# Roseta_Shield.net
KiCad netlist of a schematic drawn in Altium Designer
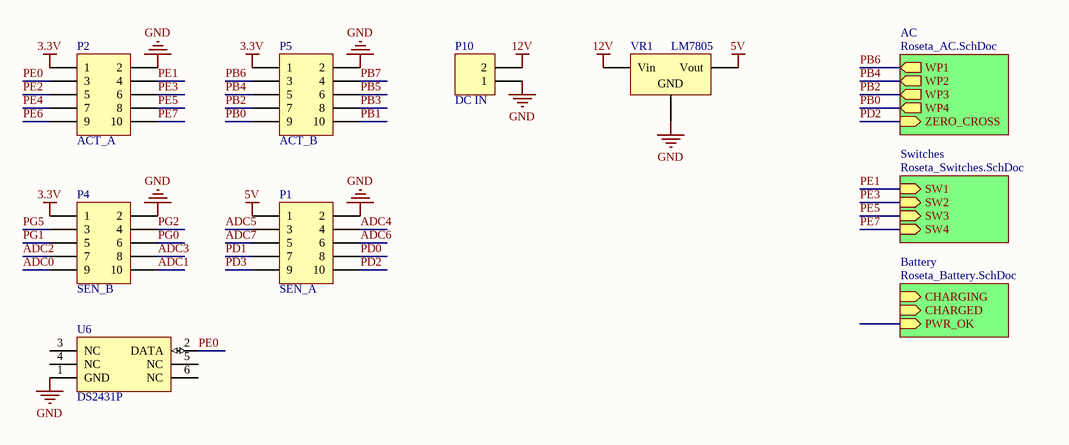
[diagram p0: Roseta_Shield.SchDoc]

(export (version "E")
  (design (tool "Eeschema 10.0.6"))
  (components
    (comp (ref "P1")
      (value "SEN_A")
      (footprint "HDR2X5_Female_Slim")
      (description "Header, 5-Pin, Dual row")
      (fields (field (name "PUBLISHER") "Altium Limited"))
      (libsource (lib "Miscellaneous Connectors") (part "Header 5X2"))
    )
    (comp (ref "P2")
      (value "ACT_A")
      (footprint "HDR2X5_Female_Slim")
      (description "Header, 5-Pin, Dual row")
      (fields (field (name "PUBLISHER") "Altium Limited"))
      (libsource (lib "Miscellaneous Connectors") (part "Header 5X2"))
    )
    (comp (ref "P4")
      (value "SEN_B")
      (footprint "HDR2X5_Female_Slim")
      (description "Header, 5-Pin, Dual row")
      (fields (field (name "PUBLISHER") "Altium Limited"))
      (libsource (lib "Miscellaneous Connectors") (part "Header 5X2"))
    )
    (comp (ref "P5")
      (value "ACT_B")
      (footprint "HDR2X5_Female_Slim")
      (description "Header, 5-Pin, Dual row")
      (fields (field (name "PUBLISHER") "Altium Limited"))
      (libsource (lib "Miscellaneous Connectors") (part "Header 5X2"))
    )
    (comp (ref "P10")
      (value "DC IN")
      (footprint "TERMINAL BLOCK X2")
      (description "Header, 2-Pin")
      (fields (field (name "PUBLISHER") "Altium Limited"))
      (libsource (lib "Miscellaneous Connectors") (part "Header 2"))
    )
    (comp (ref "U6")
      (value "DS2431P")
      (footprint "TSOC6")
      (description "256-Bit 1-Wire EEPROM")
      (fields (field (name "PUBLISHER") "Altium Limited"))
      (libsource (lib "Dallas Memory EEPROM") (part "DS2430AP"))
    )
    (comp (ref "VR1")
      (value "LM7805")
      (footprint "TO254P1510-3_4N")
      (description "Voltage Regulator")
      (fields (field (name "PUBLISHER") "Altium Limited"))
      (libsource (lib "Miscellaneous Devices") (part "Volt Reg"))
    )
  )
  (nets
    (net (code "1") (name "/ADC0") (class "Default")
      (node (ref "P4") (pin "9") (pinfunction "9_9") (pintype "passive"))
    )
    (net (code "2") (name "/ADC1") (class "Default")
      (node (ref "P4") (pin "10") (pinfunction "10_10") (pintype "passive"))
    )
    (net (code "3") (name "/ADC2") (class "Default")
      (node (ref "P4") (pin "7") (pinfunction "7_7") (pintype "passive"))
    )
    (net (code "4") (name "/ADC3") (class "Default")
      (node (ref "P4") (pin "8") (pinfunction "8_8") (pintype "passive"))
    )
    (net (code "5") (name "/ADC4") (class "Default")
      (node (ref "P1") (pin "4") (pinfunction "4_4") (pintype "passive"))
    )
    (net (code "6") (name "/ADC5") (class "Default")
      (node (ref "P1") (pin "3") (pinfunction "3_3") (pintype "passive"))
    )
    (net (code "7") (name "/ADC6") (class "Default")
      (node (ref "P1") (pin "6") (pinfunction "6_6") (pintype "passive"))
    )
    (net (code "8") (name "/ADC7") (class "Default")
      (node (ref "P1") (pin "5") (pinfunction "5_5") (pintype "passive"))
    )
    (net (code "11") (name "/PB0") (class "Default")
      (node (ref "P5") (pin "9") (pinfunction "9_9") (pintype "passive"))
    )
    (net (code "12") (name "/PB1") (class "Default")
      (node (ref "P5") (pin "10") (pinfunction "10_10") (pintype "passive"))
    )
    (net (code "13") (name "/PB2") (class "Default")
      (node (ref "P5") (pin "7") (pinfunction "7_7") (pintype "passive"))
    )
    (net (code "14") (name "/PB3") (class "Default")
      (node (ref "P5") (pin "8") (pinfunction "8_8") (pintype "passive"))
    )
    (net (code "15") (name "/PB4") (class "Default")
      (node (ref "P5") (pin "5") (pinfunction "5_5") (pintype "passive"))
    )
    (net (code "16") (name "/PB5") (class "Default")
      (node (ref "P5") (pin "6") (pinfunction "6_6") (pintype "passive"))
    )
    (net (code "17") (name "/PB6") (class "Default")
      (node (ref "P5") (pin "3") (pinfunction "3_3") (pintype "passive"))
    )
    (net (code "18") (name "/PB7") (class "Default")
      (node (ref "P5") (pin "4") (pinfunction "4_4") (pintype "passive"))
    )
    (net (code "19") (name "/PD0") (class "Default")
      (node (ref "P1") (pin "8") (pinfunction "8_8") (pintype "passive"))
    )
    (net (code "20") (name "/PD1") (class "Default")
      (node (ref "P1") (pin "7") (pinfunction "7_7") (pintype "passive"))
    )
    (net (code "21") (name "/PD2") (class "Default")
      (node (ref "P1") (pin "10") (pinfunction "10_10") (pintype "passive"))
    )
    (net (code "22") (name "/PD3") (class "Default")
      (node (ref "P1") (pin "9") (pinfunction "9_9") (pintype "passive"))
    )
    (net (code "23") (name "/PE0") (class "Default")
      (node (ref "P2") (pin "3") (pinfunction "3_3") (pintype "passive"))
      (node (ref "U6") (pin "2") (pinfunction "DATA_2") (pintype "bidirectional"))
    )
    (net (code "24") (name "/PE1") (class "Default")
      (node (ref "P2") (pin "4") (pinfunction "4_4") (pintype "passive"))
    )
    (net (code "25") (name "/PE2") (class "Default")
      (node (ref "P2") (pin "5") (pinfunction "5_5") (pintype "passive"))
    )
    (net (code "26") (name "/PE3") (class "Default")
      (node (ref "P2") (pin "6") (pinfunction "6_6") (pintype "passive"))
    )
    (net (code "27") (name "/PE4") (class "Default")
      (node (ref "P2") (pin "7") (pinfunction "7_7") (pintype "passive"))
    )
    (net (code "28") (name "/PE5") (class "Default")
      (node (ref "P2") (pin "8") (pinfunction "8_8") (pintype "passive"))
    )
    (net (code "29") (name "/PE6") (class "Default")
      (node (ref "P2") (pin "9") (pinfunction "9_9") (pintype "passive"))
    )
    (net (code "30") (name "/PE7") (class "Default")
      (node (ref "P2") (pin "10") (pinfunction "10_10") (pintype "passive"))
    )
    (net (code "31") (name "/PG0") (class "Default")
      (node (ref "P4") (pin "6") (pinfunction "6_6") (pintype "passive"))
    )
    (net (code "32") (name "/PG1") (class "Default")
      (node (ref "P4") (pin "5") (pinfunction "5_5") (pintype "passive"))
    )
    (net (code "33") (name "/PG2") (class "Default")
      (node (ref "P4") (pin "4") (pinfunction "4_4") (pintype "passive"))
    )
    (net (code "34") (name "/PG5") (class "Default")
      (node (ref "P4") (pin "3") (pinfunction "3_3") (pintype "passive"))
    )
    (net (code "36") (name "3.3V") (class "Default")
      (node (ref "P2") (pin "1") (pinfunction "1_1") (pintype "passive"))
      (node (ref "P4") (pin "1") (pinfunction "1_1") (pintype "passive"))
      (node (ref "P5") (pin "1") (pinfunction "1_1") (pintype "passive"))
    )
    (net (code "37") (name "5V") (class "Default")
      (node (ref "P1") (pin "1") (pinfunction "1_1") (pintype "passive"))
      (node (ref "VR1") (pin "3") (pinfunction "Vout_3") (pintype "passive"))
    )
    (net (code "38") (name "12V") (class "Default")
      (node (ref "P10") (pin "2") (pinfunction "2_2") (pintype "passive"))
      (node (ref "VR1") (pin "1") (pinfunction "Vin_1") (pintype "passive"))
    )
    (net (code "39") (name "GND") (class "Default")
      (node (ref "P1") (pin "2") (pinfunction "2_2") (pintype "passive"))
      (node (ref "P10") (pin "1") (pinfunction "1_1") (pintype "passive"))
      (node (ref "P2") (pin "2") (pinfunction "2_2") (pintype "passive"))
      (node (ref "P4") (pin "2") (pinfunction "2_2") (pintype "passive"))
      (node (ref "P5") (pin "2") (pinfunction "2_2") (pintype "passive"))
      (node (ref "U6") (pin "1") (pinfunction "GND_1") (pintype "power_in"))
      (node (ref "VR1") (pin "2") (pinfunction "GND_2") (pintype "passive"))
    )
    (net (code "40") (name "unconnected-(U6-NC-Pad3)") (class "Default")
      (node (ref "U6") (pin "3") (pinfunction "NC_3") (pintype "passive"))
    )
    (net (code "41") (name "unconnected-(U6-NC-Pad4)") (class "Default")
      (node (ref "U6") (pin "4") (pinfunction "NC_4") (pintype "passive"))
    )
    (net (code "42") (name "unconnected-(U6-NC-Pad5)") (class "Default")
      (node (ref "U6") (pin "5") (pinfunction "NC_5") (pintype "passive"))
    )
    (net (code "43") (name "unconnected-(U6-NC-Pad6)") (class "Default")
      (node (ref "U6") (pin "6") (pinfunction "NC_6") (pintype "passive"))
    )
  )
)
